# toppanel2.net
KiCad netlist of a schematic drawn in EAGLE
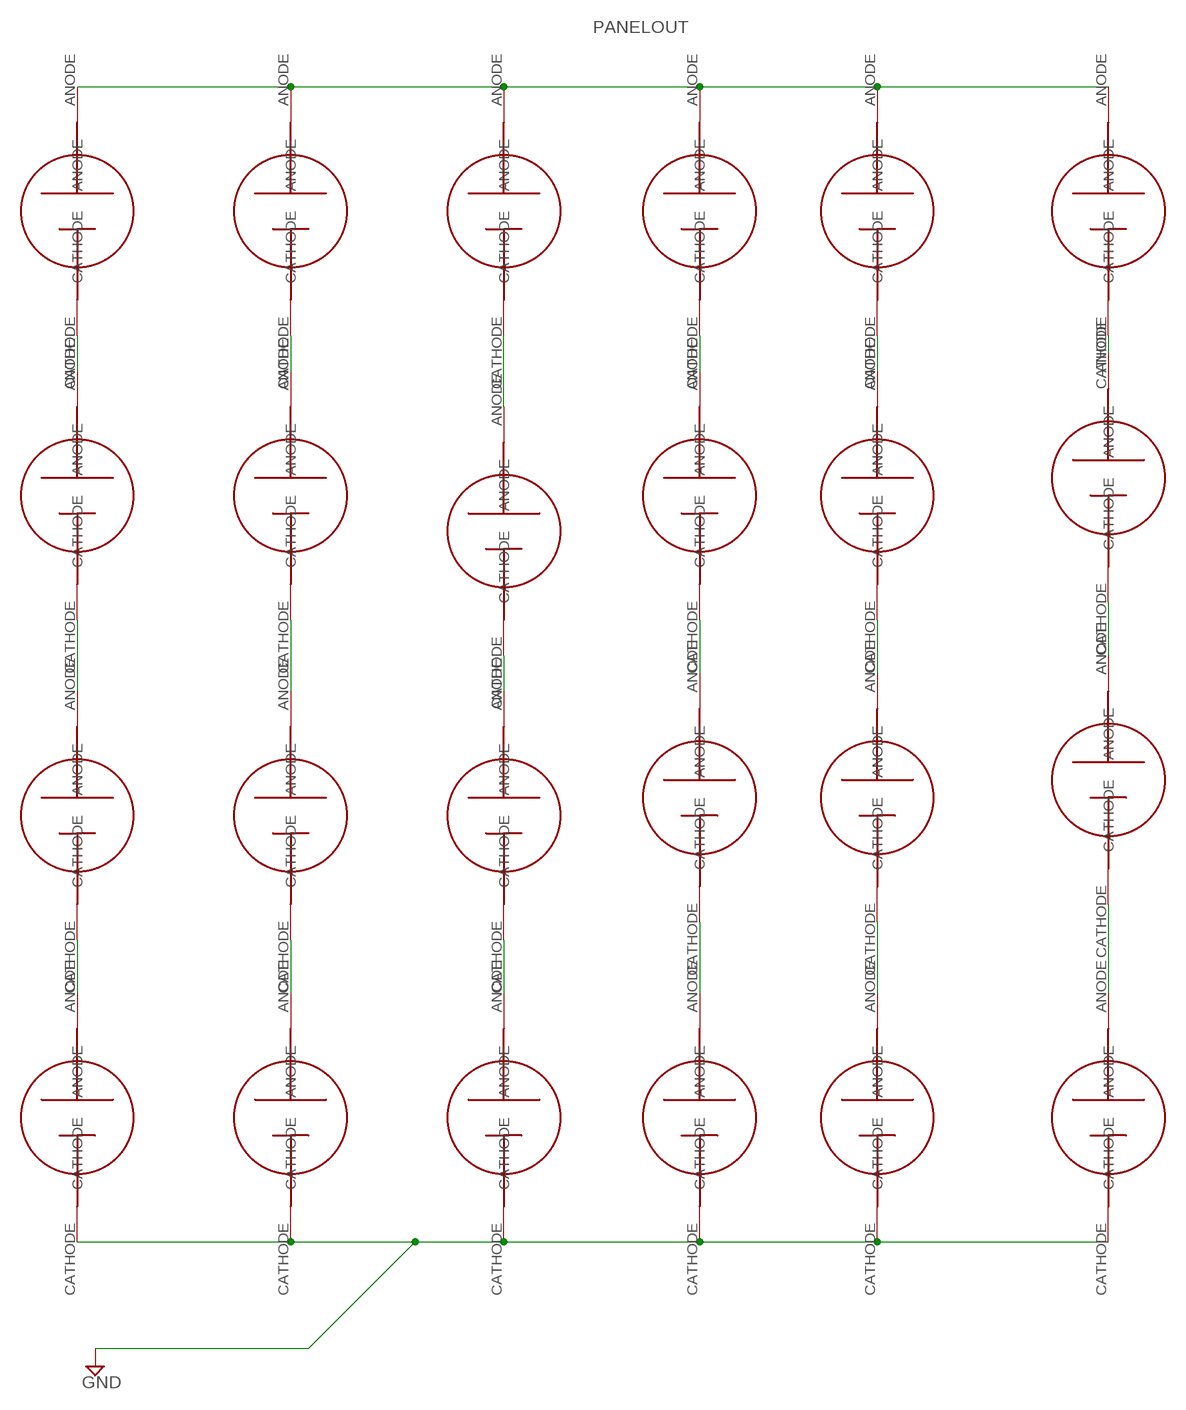
[diagram p0: schematic, sheet 1]

(export (version "E")
  (design (tool "Eeschema 10.0.6"))
  (components
    (comp (ref "1A")
      (value "SOLARCELL")
      (footprint "eagle-import:SOLARCELL")
      (libsource (lib "eagle-import") (part "SOLARCELL"))
    )
    (comp (ref "1B")
      (value "SOLARCELL")
      (footprint "eagle-import:SOLARCELL")
      (libsource (lib "eagle-import") (part "SOLARCELL"))
    )
    (comp (ref "1C")
      (value "SOLARCELL")
      (footprint "eagle-import:SOLARCELL")
      (libsource (lib "eagle-import") (part "SOLARCELL"))
    )
    (comp (ref "1D")
      (value "SOLARCELL")
      (footprint "eagle-import:SOLARCELL")
      (libsource (lib "eagle-import") (part "SOLARCELL"))
    )
    (comp (ref "2A")
      (value "SOLARCELL")
      (footprint "eagle-import:SOLARCELL")
      (libsource (lib "eagle-import") (part "SOLARCELL"))
    )
    (comp (ref "2B")
      (value "SOLARCELL")
      (footprint "eagle-import:SOLARCELL")
      (libsource (lib "eagle-import") (part "SOLARCELL"))
    )
    (comp (ref "2C")
      (value "SOLARCELL")
      (footprint "eagle-import:SOLARCELL")
      (libsource (lib "eagle-import") (part "SOLARCELL"))
    )
    (comp (ref "2D")
      (value "SOLARCELL")
      (footprint "eagle-import:SOLARCELL")
      (libsource (lib "eagle-import") (part "SOLARCELL"))
    )
    (comp (ref "3A")
      (value "SOLARCELL")
      (footprint "eagle-import:SOLARCELL")
      (libsource (lib "eagle-import") (part "SOLARCELL"))
    )
    (comp (ref "3B")
      (value "SOLARCELL")
      (footprint "eagle-import:SOLARCELL")
      (libsource (lib "eagle-import") (part "SOLARCELL"))
    )
    (comp (ref "3C")
      (value "SOLARCELL")
      (footprint "eagle-import:SOLARCELL")
      (libsource (lib "eagle-import") (part "SOLARCELL"))
    )
    (comp (ref "3D")
      (value "SOLARCELL")
      (footprint "eagle-import:SOLARCELL")
      (libsource (lib "eagle-import") (part "SOLARCELL"))
    )
    (comp (ref "4A")
      (value "SOLARCELL")
      (footprint "eagle-import:SOLARCELL")
      (libsource (lib "eagle-import") (part "SOLARCELL"))
    )
    (comp (ref "4B")
      (value "SOLARCELL")
      (footprint "eagle-import:SOLARCELL")
      (libsource (lib "eagle-import") (part "SOLARCELL"))
    )
    (comp (ref "4C")
      (value "SOLARCELL")
      (footprint "eagle-import:SOLARCELL")
      (libsource (lib "eagle-import") (part "SOLARCELL"))
    )
    (comp (ref "4D")
      (value "SOLARCELL")
      (footprint "eagle-import:SOLARCELL")
      (libsource (lib "eagle-import") (part "SOLARCELL"))
    )
    (comp (ref "5A")
      (value "SOLARCELL")
      (footprint "eagle-import:SOLARCELL")
      (libsource (lib "eagle-import") (part "SOLARCELL"))
    )
    (comp (ref "5B")
      (value "SOLARCELL")
      (footprint "eagle-import:SOLARCELL")
      (libsource (lib "eagle-import") (part "SOLARCELL"))
    )
    (comp (ref "5C")
      (value "SOLARCELL")
      (footprint "eagle-import:SOLARCELL")
      (libsource (lib "eagle-import") (part "SOLARCELL"))
    )
    (comp (ref "5D")
      (value "SOLARCELL")
      (footprint "eagle-import:SOLARCELL")
      (libsource (lib "eagle-import") (part "SOLARCELL"))
    )
    (comp (ref "6A")
      (value "SOLARCELL")
      (footprint "eagle-import:SOLARCELL")
      (libsource (lib "eagle-import") (part "SOLARCELL"))
    )
    (comp (ref "6B")
      (value "SOLARCELL")
      (footprint "eagle-import:SOLARCELL")
      (libsource (lib "eagle-import") (part "SOLARCELL"))
    )
    (comp (ref "6C")
      (value "SOLARCELL")
      (footprint "eagle-import:SOLARCELL")
      (libsource (lib "eagle-import") (part "SOLARCELL"))
    )
    (comp (ref "6D")
      (value "SOLARCELL")
      (footprint "eagle-import:SOLARCELL")
      (libsource (lib "eagle-import") (part "SOLARCELL"))
    )
  )
  (nets
    (net (code "1") (name "/PANELOUT") (class "Default")
      (node (ref "1D") (pin "ANODE") (pinfunction "ANODE_ANODE") (pintype "bidirectional"))
      (node (ref "2D") (pin "ANODE") (pinfunction "ANODE_ANODE") (pintype "bidirectional"))
      (node (ref "3D") (pin "ANODE") (pinfunction "ANODE_ANODE") (pintype "bidirectional"))
      (node (ref "4D") (pin "ANODE") (pinfunction "ANODE_ANODE") (pintype "bidirectional"))
      (node (ref "5D") (pin "ANODE") (pinfunction "ANODE_ANODE") (pintype "bidirectional"))
      (node (ref "6D") (pin "ANODE") (pinfunction "ANODE_ANODE") (pintype "bidirectional"))
    )
    (net (code "2") (name "GND") (class "Default")
      (node (ref "1A") (pin "CATHODE") (pinfunction "CATHODE_CATHODE") (pintype "bidirectional"))
      (node (ref "2A") (pin "CATHODE") (pinfunction "CATHODE_CATHODE") (pintype "bidirectional"))
      (node (ref "3A") (pin "CATHODE") (pinfunction "CATHODE_CATHODE") (pintype "bidirectional"))
      (node (ref "4A") (pin "CATHODE") (pinfunction "CATHODE_CATHODE") (pintype "bidirectional"))
      (node (ref "5A") (pin "CATHODE") (pinfunction "CATHODE_CATHODE") (pintype "bidirectional"))
      (node (ref "6A") (pin "CATHODE") (pinfunction "CATHODE_CATHODE") (pintype "bidirectional"))
    )
    (net (code "3") (name "Net-(1A-PadANODE)") (class "Default")
      (node (ref "1A") (pin "ANODE") (pinfunction "ANODE_ANODE") (pintype "bidirectional"))
      (node (ref "1B") (pin "CATHODE") (pinfunction "CATHODE_CATHODE") (pintype "bidirectional"))
    )
    (net (code "4") (name "Net-(1B-PadANODE)") (class "Default")
      (node (ref "1B") (pin "ANODE") (pinfunction "ANODE_ANODE") (pintype "bidirectional"))
      (node (ref "1C") (pin "CATHODE") (pinfunction "CATHODE_CATHODE") (pintype "bidirectional"))
    )
    (net (code "5") (name "Net-(1C-PadANODE)") (class "Default")
      (node (ref "1C") (pin "ANODE") (pinfunction "ANODE_ANODE") (pintype "bidirectional"))
      (node (ref "1D") (pin "CATHODE") (pinfunction "CATHODE_CATHODE") (pintype "bidirectional"))
    )
    (net (code "6") (name "Net-(2A-PadANODE)") (class "Default")
      (node (ref "2A") (pin "ANODE") (pinfunction "ANODE_ANODE") (pintype "bidirectional"))
      (node (ref "2B") (pin "CATHODE") (pinfunction "CATHODE_CATHODE") (pintype "bidirectional"))
    )
    (net (code "7") (name "Net-(2B-PadANODE)") (class "Default")
      (node (ref "2B") (pin "ANODE") (pinfunction "ANODE_ANODE") (pintype "bidirectional"))
      (node (ref "2C") (pin "CATHODE") (pinfunction "CATHODE_CATHODE") (pintype "bidirectional"))
    )
    (net (code "8") (name "Net-(2C-PadANODE)") (class "Default")
      (node (ref "2C") (pin "ANODE") (pinfunction "ANODE_ANODE") (pintype "bidirectional"))
      (node (ref "2D") (pin "CATHODE") (pinfunction "CATHODE_CATHODE") (pintype "bidirectional"))
    )
    (net (code "9") (name "Net-(3A-PadANODE)") (class "Default")
      (node (ref "3A") (pin "ANODE") (pinfunction "ANODE_ANODE") (pintype "bidirectional"))
      (node (ref "3B") (pin "CATHODE") (pinfunction "CATHODE_CATHODE") (pintype "bidirectional"))
    )
    (net (code "10") (name "Net-(3B-PadANODE)") (class "Default")
      (node (ref "3B") (pin "ANODE") (pinfunction "ANODE_ANODE") (pintype "bidirectional"))
      (node (ref "3C") (pin "CATHODE") (pinfunction "CATHODE_CATHODE") (pintype "bidirectional"))
    )
    (net (code "11") (name "Net-(3C-PadANODE)") (class "Default")
      (node (ref "3C") (pin "ANODE") (pinfunction "ANODE_ANODE") (pintype "bidirectional"))
      (node (ref "3D") (pin "CATHODE") (pinfunction "CATHODE_CATHODE") (pintype "bidirectional"))
    )
    (net (code "12") (name "Net-(4A-PadANODE)") (class "Default")
      (node (ref "4A") (pin "ANODE") (pinfunction "ANODE_ANODE") (pintype "bidirectional"))
      (node (ref "4B") (pin "CATHODE") (pinfunction "CATHODE_CATHODE") (pintype "bidirectional"))
    )
    (net (code "13") (name "Net-(4B-PadANODE)") (class "Default")
      (node (ref "4B") (pin "ANODE") (pinfunction "ANODE_ANODE") (pintype "bidirectional"))
      (node (ref "4C") (pin "CATHODE") (pinfunction "CATHODE_CATHODE") (pintype "bidirectional"))
    )
    (net (code "14") (name "Net-(4C-PadANODE)") (class "Default")
      (node (ref "4C") (pin "ANODE") (pinfunction "ANODE_ANODE") (pintype "bidirectional"))
      (node (ref "4D") (pin "CATHODE") (pinfunction "CATHODE_CATHODE") (pintype "bidirectional"))
    )
    (net (code "15") (name "Net-(5A-PadANODE)") (class "Default")
      (node (ref "5A") (pin "ANODE") (pinfunction "ANODE_ANODE") (pintype "bidirectional"))
      (node (ref "5B") (pin "CATHODE") (pinfunction "CATHODE_CATHODE") (pintype "bidirectional"))
    )
    (net (code "16") (name "Net-(5B-PadANODE)") (class "Default")
      (node (ref "5B") (pin "ANODE") (pinfunction "ANODE_ANODE") (pintype "bidirectional"))
      (node (ref "5C") (pin "CATHODE") (pinfunction "CATHODE_CATHODE") (pintype "bidirectional"))
    )
    (net (code "17") (name "Net-(5C-PadANODE)") (class "Default")
      (node (ref "5C") (pin "ANODE") (pinfunction "ANODE_ANODE") (pintype "bidirectional"))
      (node (ref "5D") (pin "CATHODE") (pinfunction "CATHODE_CATHODE") (pintype "bidirectional"))
    )
    (net (code "18") (name "Net-(6A-PadANODE)") (class "Default")
      (node (ref "6A") (pin "ANODE") (pinfunction "ANODE_ANODE") (pintype "bidirectional"))
      (node (ref "6B") (pin "CATHODE") (pinfunction "CATHODE_CATHODE") (pintype "bidirectional"))
    )
    (net (code "19") (name "Net-(6B-PadANODE)") (class "Default")
      (node (ref "6B") (pin "ANODE") (pinfunction "ANODE_ANODE") (pintype "bidirectional"))
      (node (ref "6C") (pin "CATHODE") (pinfunction "CATHODE_CATHODE") (pintype "bidirectional"))
    )
    (net (code "20") (name "Net-(6C-PadANODE)") (class "Default")
      (node (ref "6C") (pin "ANODE") (pinfunction "ANODE_ANODE") (pintype "bidirectional"))
      (node (ref "6D") (pin "CATHODE") (pinfunction "CATHODE_CATHODE") (pintype "bidirectional"))
    )
  )
)
